# Sheet1_testes.net
KiCad netlist of a schematic drawn in Altium Designer
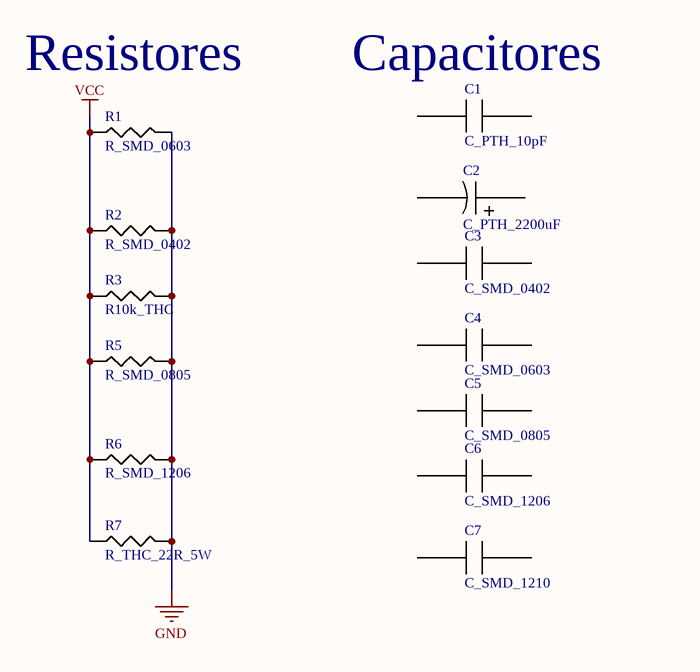
[diagram p0: Sheet1_testes.SchDoc]

(export (version "E")
  (design (tool "Eeschema 10.0.6"))
  (components
    (comp (ref "C1")
      (value "C_PTH_10pF")
      (footprint "C_PTH_10pF")
      (libsource (lib "CapacitoresLA2i_2") (part "C_PTH_10pF"))
    )
    (comp (ref "C2")
      (value "C_PTH_2200uF")
      (footprint "C_PTH_2200uF")
      (libsource (lib "CapacitoresLA2i_2") (part "C_PTH_2200uF"))
    )
    (comp (ref "C3")
      (value "C_SMD_0402")
      (footprint "C_SMD_0402")
      (libsource (lib "CapacitoresLA2i_2") (part "C_SMD_0402"))
    )
    (comp (ref "C4")
      (value "C_SMD_0603")
      (footprint "C_SMD_0603")
      (libsource (lib "CapacitoresLA2i_2") (part "C_SMD_0603"))
    )
    (comp (ref "C5")
      (value "C_SMD_0805")
      (footprint "C_SMD_0805")
      (libsource (lib "CapacitoresLA2i_2") (part "C_SMD_0805"))
    )
    (comp (ref "C6")
      (value "C_SMD_1206")
      (footprint "C_SMD_1206")
      (libsource (lib "CapacitoresLA2i_2") (part "C_SMD_1206"))
    )
    (comp (ref "C7")
      (value "C_SMD_1210")
      (footprint "C_SMD_1210")
      (libsource (lib "CapacitoresLA2i_2") (part "C_SMD_1210"))
    )
    (comp (ref "R1")
      (value "R_SMD_0603")
      (footprint "R_SMD_0603")
      (libsource (lib "Resistores") (part "R_SMD_0603"))
    )
    (comp (ref "R2")
      (value "R_SMD_0402")
      (footprint "R_SMD_0402")
      (libsource (lib "Resistores") (part "R_SMD_0402"))
    )
    (comp (ref "R3")
      (value "R10k_THC")
      (footprint "R_THC_10k")
      (libsource (lib "Resistores") (part "R10k_THC"))
    )
    (comp (ref "R5")
      (value "R_SMD_0805")
      (footprint "R_SMD_0805")
      (libsource (lib "Resistores") (part "R_SMD_0805"))
    )
    (comp (ref "R6")
      (value "R_SMD_1206")
      (footprint "R_SMD_1206")
      (libsource (lib "Resistores") (part "R_SMD_1206"))
    )
    (comp (ref "R7")
      (value "R_THC_22R_5W")
      (footprint "R_THC_22R_5W")
      (libsource (lib "Resistores") (part "R_THC_22R_5W"))
    )
  )
  (nets
    (net (code "1") (name "GND") (class "Default")
      (node (ref "R1") (pin "2") (pinfunction "2_2") (pintype "passive"))
      (node (ref "R2") (pin "2") (pinfunction "2_2") (pintype "passive"))
      (node (ref "R3") (pin "2") (pinfunction "2_2") (pintype "passive"))
      (node (ref "R5") (pin "2") (pinfunction "2_2") (pintype "passive"))
      (node (ref "R6") (pin "2") (pinfunction "2_2") (pintype "passive"))
      (node (ref "R7") (pin "2") (pinfunction "2_2") (pintype "passive"))
    )
    (net (code "2") (name "VCC") (class "Default")
      (node (ref "R1") (pin "1") (pinfunction "1_1") (pintype "passive"))
      (node (ref "R2") (pin "1") (pinfunction "1_1") (pintype "passive"))
      (node (ref "R3") (pin "1") (pinfunction "1_1") (pintype "passive"))
      (node (ref "R5") (pin "1") (pinfunction "1_1") (pintype "passive"))
      (node (ref "R6") (pin "1") (pinfunction "1_1") (pintype "passive"))
      (node (ref "R7") (pin "1") (pinfunction "1_1") (pintype "passive"))
    )
    (net (code "3") (name "unconnected-(C1-Pad1)") (class "Default")
      (node (ref "C1") (pin "1") (pinfunction "1_1") (pintype "passive"))
    )
    (net (code "4") (name "unconnected-(C1-Pad2)") (class "Default")
      (node (ref "C1") (pin "2") (pinfunction "2_2") (pintype "passive"))
    )
    (net (code "5") (name "unconnected-(C2-Pad1)") (class "Default")
      (node (ref "C2") (pin "1") (pinfunction "1_1") (pintype "passive"))
    )
    (net (code "6") (name "unconnected-(C2-Pad2)") (class "Default")
      (node (ref "C2") (pin "2") (pinfunction "2_2") (pintype "passive"))
    )
    (net (code "7") (name "unconnected-(C3-Pad1)") (class "Default")
      (node (ref "C3") (pin "1") (pinfunction "1_1") (pintype "passive"))
    )
    (net (code "8") (name "unconnected-(C3-Pad2)") (class "Default")
      (node (ref "C3") (pin "2") (pinfunction "2_2") (pintype "passive"))
    )
    (net (code "9") (name "unconnected-(C4-Pad1)") (class "Default")
      (node (ref "C4") (pin "1") (pinfunction "1_1") (pintype "passive"))
    )
    (net (code "10") (name "unconnected-(C4-Pad2)") (class "Default")
      (node (ref "C4") (pin "2") (pinfunction "2_2") (pintype "passive"))
    )
    (net (code "11") (name "unconnected-(C5-Pad1)") (class "Default")
      (node (ref "C5") (pin "1") (pinfunction "1_1") (pintype "passive"))
    )
    (net (code "12") (name "unconnected-(C5-Pad2)") (class "Default")
      (node (ref "C5") (pin "2") (pinfunction "2_2") (pintype "passive"))
    )
    (net (code "13") (name "unconnected-(C6-Pad1)") (class "Default")
      (node (ref "C6") (pin "1") (pinfunction "1_1") (pintype "passive"))
    )
    (net (code "14") (name "unconnected-(C6-Pad2)") (class "Default")
      (node (ref "C6") (pin "2") (pinfunction "2_2") (pintype "passive"))
    )
    (net (code "15") (name "unconnected-(C7-Pad1)") (class "Default")
      (node (ref "C7") (pin "1") (pinfunction "1_1") (pintype "passive"))
    )
    (net (code "16") (name "unconnected-(C7-Pad2)") (class "Default")
      (node (ref "C7") (pin "2") (pinfunction "2_2") (pintype "passive"))
    )
  )
)
